# Power_Generation_-_Connector.net
KiCad netlist of a schematic drawn in Altium Designer
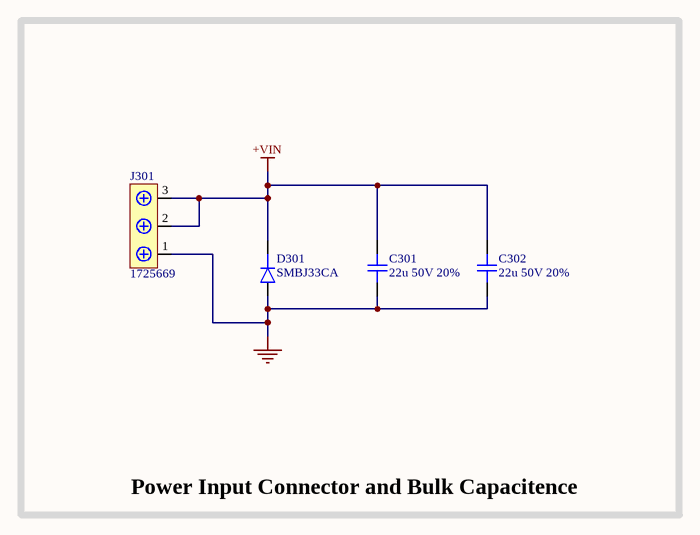
[diagram p0: Power Generation - Connector.SchDoc]

(export (version "E")
  (design (tool "Eeschema 10.0.6"))
  (components
    (comp (ref "C301")
      (value "22u 50V 20%")
      (footprint "CAP-EL-NP-5MM")
      (description "Capacitor SMD Electrolytic Non-Polarised 5mm Diameter")
      (fields
        (field (name "MANUFACTURER") "PANASONIC")
        (field (name "MANUFACTURER PART NUMBER") "EEEFT1H220AR")
      )
      (libsource (lib "Schematic-Lib") (part "CAP_EL_NP_5MM"))
    )
    (comp (ref "C302")
      (value "22u 50V 20%")
      (footprint "CAP-EL-NP-5MM")
      (description "Capacitor SMD Electrolytic Non-Polarised 5mm Diameter")
      (fields
        (field (name "MANUFACTURER") "PANASONIC")
        (field (name "MANUFACTURER PART NUMBER") "EEEFT1H220AR")
      )
      (libsource (lib "Schematic-Lib") (part "CAP_EL_NP_5MM"))
    )
    (comp (ref "D301")
      (value "SMBJ33CA")
      (footprint "DO-214AC-2 (SMA)")
      (description "Diode SMD SMA (DO-214AA)")
      (fields (field (name "MANUFACTURER") "Littelfuse"))
      (libsource (lib "Schematic-Lib") (part "D_SMA"))
    )
    (comp (ref "J301")
      (value "1725669")
      (footprint "1725669")
      (description "Screw Terminal Block 3 Positions 2.54mm")
      (fields (field (name "MANUFACTURER") "Phoenix"))
      (libsource (lib "Schematic-Lib") (part "1725669"))
    )
  )
  (nets
    (net (code "1") (name "+VIN") (class "Default")
      (node (ref "C301") (pin "1") (pinfunction "1_1") (pintype "passive"))
      (node (ref "C302") (pin "1") (pinfunction "1_1") (pintype "passive"))
      (node (ref "D301") (pin "K") (pinfunction "K_K") (pintype "passive"))
      (node (ref "J301") (pin "2") (pinfunction "2_2") (pintype "passive"))
      (node (ref "J301") (pin "3") (pinfunction "3_3") (pintype "passive"))
    )
    (net (code "2") (name "GND") (class "Default")
      (node (ref "C301") (pin "2") (pinfunction "2_2") (pintype "passive"))
      (node (ref "C302") (pin "2") (pinfunction "2_2") (pintype "passive"))
      (node (ref "D301") (pin "A") (pinfunction "A_A") (pintype "passive"))
      (node (ref "J301") (pin "1") (pinfunction "1_1") (pintype "passive"))
    )
  )
)
